# bms-interface_interface.net
KiCad netlist of a schematic drawn in Altium Designer
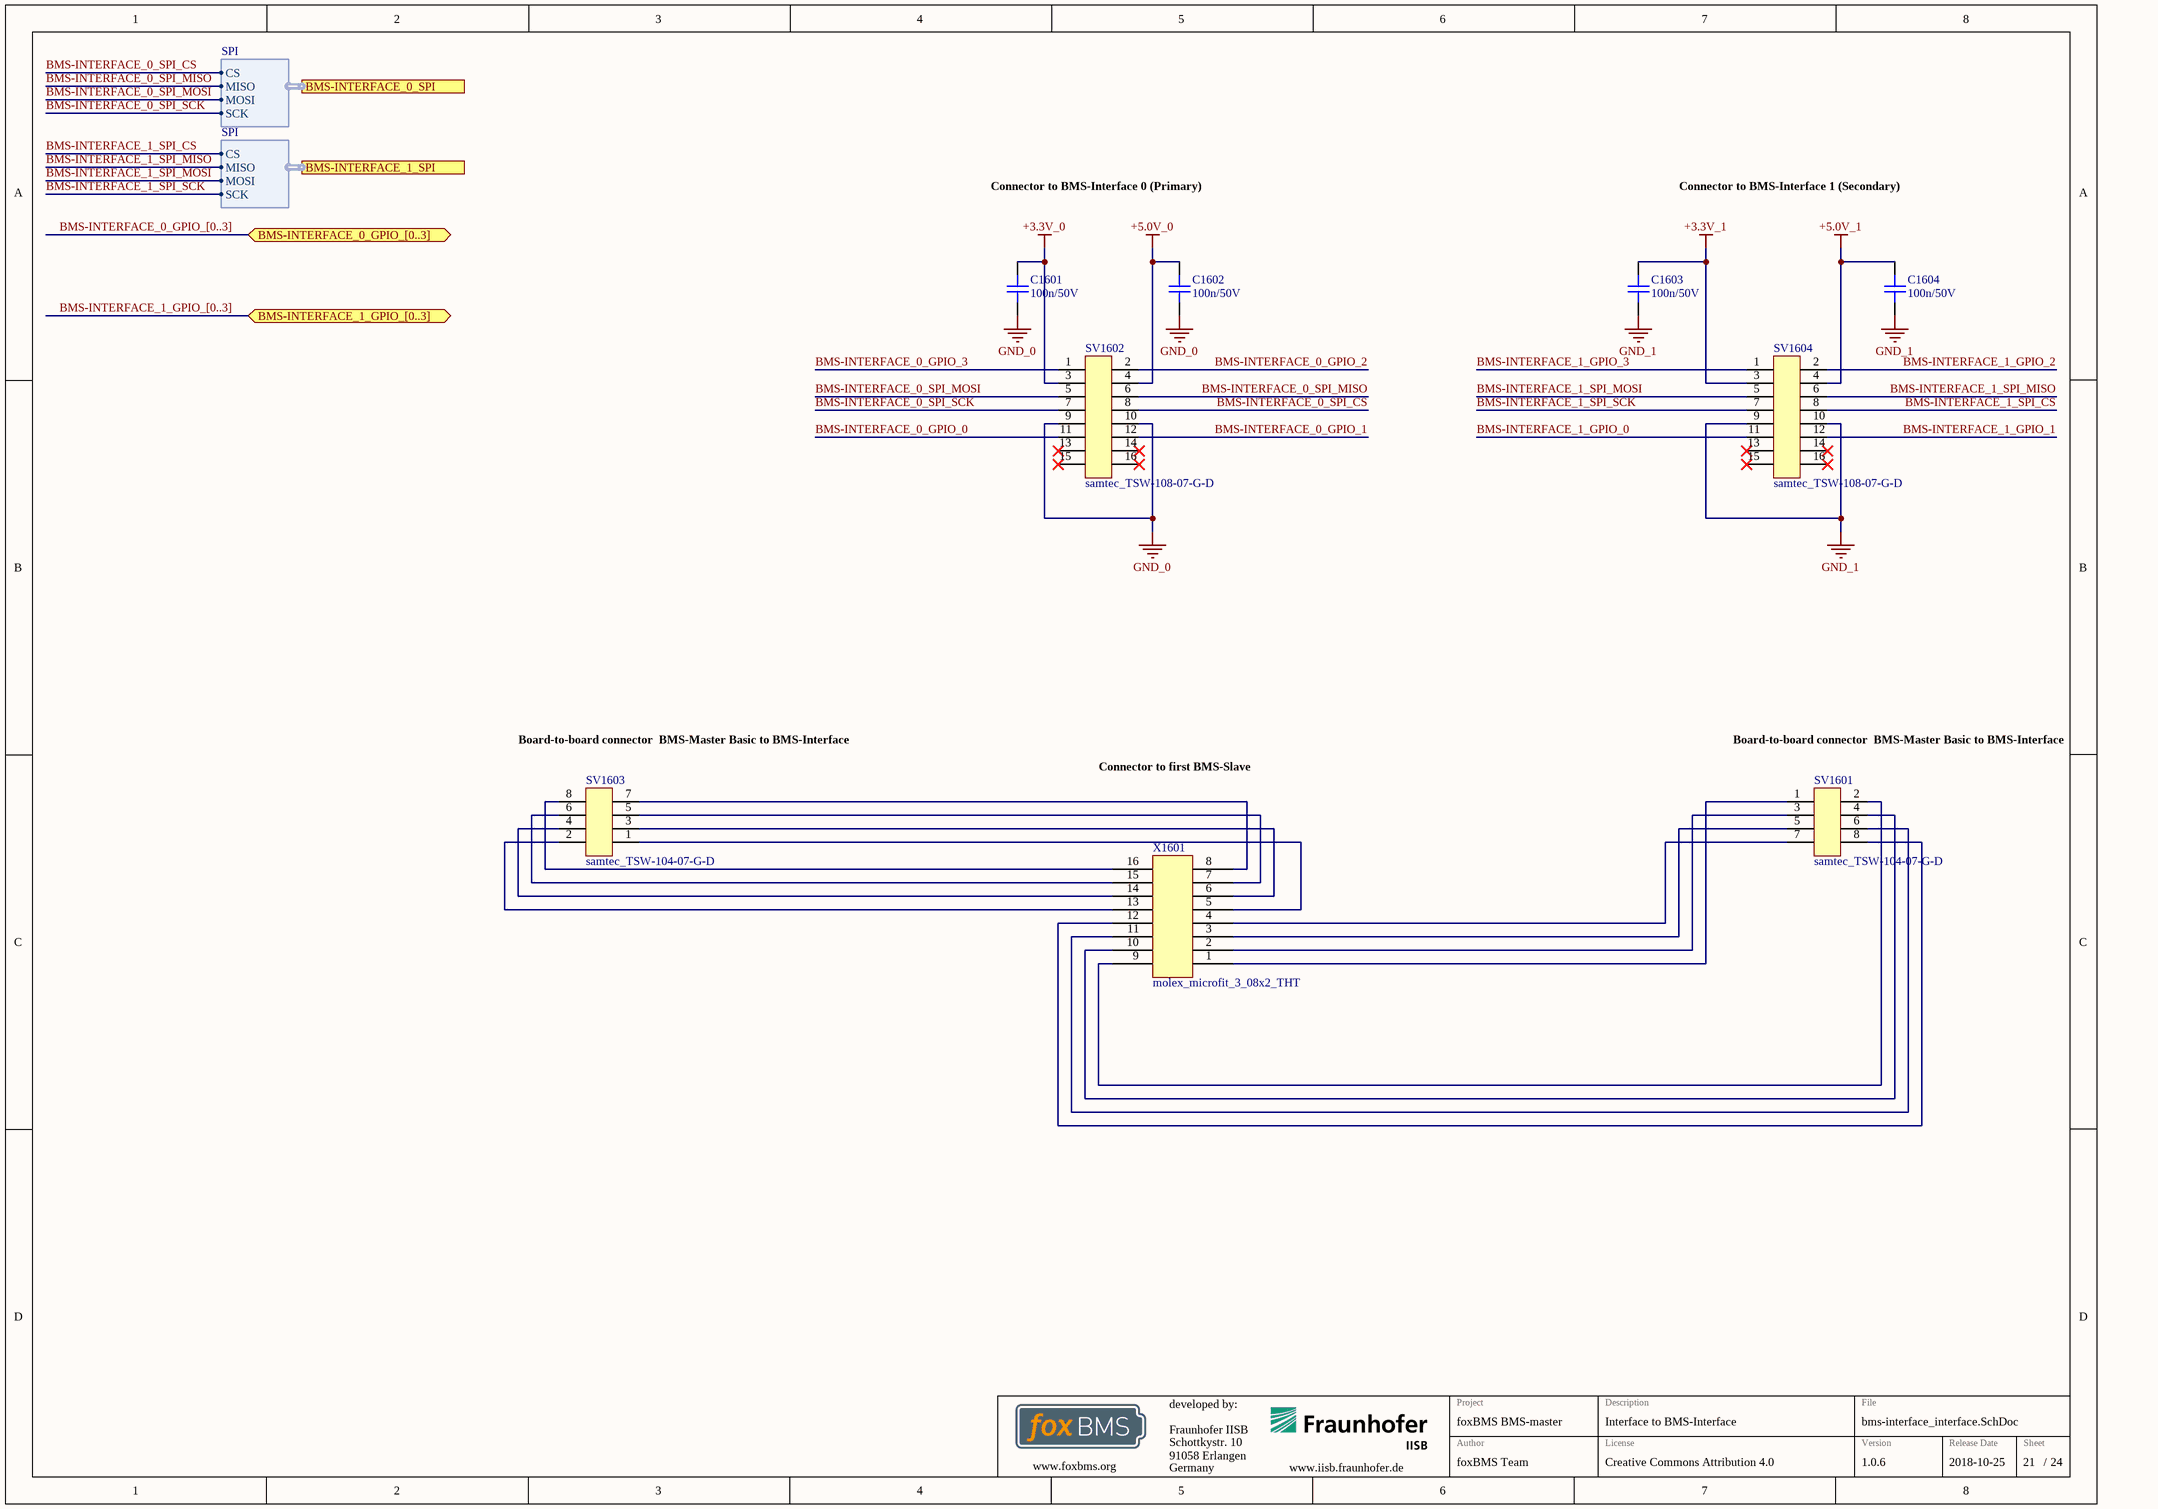
[diagram p0: bms-interface_interface.SchDoc]

(export (version "E")
  (design (tool "Eeschema 10.0.6"))
  (components
    (comp (ref "C1601")
      (value "100n/50V")
      (footprint "CAPC1608X08N")
      (description "MLCC")
      (fields (field (name "PART NUMBER") "gen_C_ceramic_100n_50V_X7R_0603"))
      (libsource (lib "OE750") (part "C"))
    )
    (comp (ref "C1602")
      (value "100n/50V")
      (footprint "CAPC1608X08N")
      (description "MLCC")
      (fields (field (name "PART NUMBER") "gen_C_ceramic_100n_50V_X7R_0603"))
      (libsource (lib "OE750") (part "C"))
    )
    (comp (ref "C1603")
      (value "100n/50V")
      (footprint "CAPC1608X08N")
      (description "MLCC")
      (fields (field (name "PART NUMBER") "gen_C_ceramic_100n_50V_X7R_0603"))
      (libsource (lib "OE750") (part "C"))
    )
    (comp (ref "C1604")
      (value "100n/50V")
      (footprint "CAPC1608X08N")
      (description "MLCC")
      (fields (field (name "PART NUMBER") "gen_C_ceramic_100n_50V_X7R_0603"))
      (libsource (lib "OE750") (part "C"))
    )
    (comp (ref "SV1601")
      (value "samtec_TSW-104-07-G-D")
      (footprint "Pinheader_2.54_2x4")
      (description "Board-To-Board Connector, Vertical, 2.54 mm, 8 Contacts, Header, TSW Series, Through Hole, 2 Rows")
      (fields (field (name "MANUFACTURER") "Samtec"))
      (libsource (lib "OE750") (part "X2x4"))
    )
    (comp (ref "SV1602")
      (value "samtec_TSW-108-07-G-D")
      (footprint "Pinheader_2.54_2x8")
      (description "Board-To-Board Connector, Vertical, 2.54 mm, 16 Contacts, Header, TSW Series, Through Hole, 2 Rows")
      (fields (field (name "MANUFACTURER") "Samtec"))
      (libsource (lib "OE750") (part "X2x8"))
    )
    (comp (ref "SV1603")
      (value "samtec_TSW-104-07-G-D")
      (footprint "Pinheader_2.54_2x4")
      (description "Board-To-Board Connector, Vertical, 2.54 mm, 8 Contacts, Header, TSW Series, Through Hole, 2 Rows")
      (fields (field (name "MANUFACTURER") "Samtec"))
      (libsource (lib "") (part "X2x4_1"))
    )
    (comp (ref "SV1604")
      (value "samtec_TSW-108-07-G-D")
      (footprint "Pinheader_2.54_2x8")
      (description "Board-To-Board Connector, Vertical, 2.54 mm, 16 Contacts, Header, TSW Series, Through Hole, 2 Rows")
      (fields (field (name "MANUFACTURER") "Samtec"))
      (libsource (lib "OE750") (part "X2x8"))
    )
    (comp (ref "X1601")
      (value "molex_microfit_3_08x2_THT")
      (footprint "MOLEX_MICROFIT_08x2_THT")
      (fields (field (name "MANUFACTURER") "Molex"))
      (libsource (lib "OE750") (part "X8x2"))
    )
  )
  (nets
    (net (code "2") (name "+3.3V_0") (class "Default")
      (node (ref "C1601") (pin "1") (pinfunction "1_1") (pintype "passive"))
      (node (ref "SV1602") (pin "3") (pintype "passive"))
    )
    (net (code "3") (name "+3.3V_1") (class "Default")
      (node (ref "C1603") (pin "1") (pinfunction "1_1") (pintype "passive"))
      (node (ref "SV1604") (pin "3") (pintype "passive"))
    )
    (net (code "4") (name "+5.0V_0") (class "Default")
      (node (ref "C1602") (pin "1") (pinfunction "1_1") (pintype "passive"))
      (node (ref "SV1602") (pin "4") (pintype "passive"))
    )
    (net (code "5") (name "+5.0V_1") (class "Default")
      (node (ref "C1604") (pin "1") (pinfunction "1_1") (pintype "passive"))
      (node (ref "SV1604") (pin "4") (pintype "passive"))
    )
    (net (code "6") (name "/BMS-INTERFACE_0_GPIO_0") (class "Default")
      (node (ref "SV1602") (pin "11") (pintype "passive"))
    )
    (net (code "7") (name "/BMS-INTERFACE_0_GPIO_1") (class "Default")
      (node (ref "SV1602") (pin "12") (pintype "passive"))
    )
    (net (code "8") (name "/BMS-INTERFACE_0_GPIO_2") (class "Default")
      (node (ref "SV1602") (pin "2") (pintype "passive"))
    )
    (net (code "9") (name "/BMS-INTERFACE_0_GPIO_3") (class "Default")
      (node (ref "SV1602") (pin "1") (pintype "passive"))
    )
    (net (code "11") (name "/BMS-INTERFACE_0_SPI_CS") (class "Default")
      (node (ref "SV1602") (pin "8") (pintype "passive"))
    )
    (net (code "12") (name "/BMS-INTERFACE_0_SPI_MISO") (class "Default")
      (node (ref "SV1602") (pin "6") (pintype "passive"))
    )
    (net (code "13") (name "/BMS-INTERFACE_0_SPI_MOSI") (class "Default")
      (node (ref "SV1602") (pin "5") (pintype "passive"))
    )
    (net (code "14") (name "/BMS-INTERFACE_0_SPI_SCK") (class "Default")
      (node (ref "SV1602") (pin "7") (pintype "passive"))
    )
    (net (code "15") (name "/BMS-INTERFACE_1_GPIO_0") (class "Default")
      (node (ref "SV1604") (pin "11") (pintype "passive"))
    )
    (net (code "16") (name "/BMS-INTERFACE_1_GPIO_1") (class "Default")
      (node (ref "SV1604") (pin "12") (pintype "passive"))
    )
    (net (code "17") (name "/BMS-INTERFACE_1_GPIO_2") (class "Default")
      (node (ref "SV1604") (pin "2") (pintype "passive"))
    )
    (net (code "18") (name "/BMS-INTERFACE_1_GPIO_3") (class "Default")
      (node (ref "SV1604") (pin "1") (pintype "passive"))
    )
    (net (code "20") (name "/BMS-INTERFACE_1_SPI_CS") (class "Default")
      (node (ref "SV1604") (pin "8") (pintype "passive"))
    )
    (net (code "21") (name "/BMS-INTERFACE_1_SPI_MISO") (class "Default")
      (node (ref "SV1604") (pin "6") (pintype "passive"))
    )
    (net (code "22") (name "/BMS-INTERFACE_1_SPI_MOSI") (class "Default")
      (node (ref "SV1604") (pin "5") (pintype "passive"))
    )
    (net (code "23") (name "/BMS-INTERFACE_1_SPI_SCK") (class "Default")
      (node (ref "SV1604") (pin "7") (pintype "passive"))
    )
    (net (code "25") (name "GND_0") (class "Default")
      (node (ref "C1601") (pin "2") (pinfunction "2_2") (pintype "passive"))
      (node (ref "C1602") (pin "2") (pinfunction "2_2") (pintype "passive"))
      (node (ref "SV1602") (pin "10") (pintype "passive"))
      (node (ref "SV1602") (pin "9") (pintype "passive"))
    )
    (net (code "26") (name "GND_1") (class "Default")
      (node (ref "C1603") (pin "2") (pinfunction "2_2") (pintype "passive"))
      (node (ref "C1604") (pin "2") (pinfunction "2_2") (pintype "passive"))
      (node (ref "SV1604") (pin "10") (pintype "passive"))
      (node (ref "SV1604") (pin "9") (pintype "passive"))
    )
    (net (code "27") (name "Net-(SV1601-Pad1)") (class "Default")
      (node (ref "SV1601") (pin "1") (pintype "passive"))
      (node (ref "X1601") (pin "1") (pintype "passive"))
    )
    (net (code "28") (name "Net-(SV1601-Pad2)") (class "Default")
      (node (ref "SV1601") (pin "2") (pintype "passive"))
      (node (ref "X1601") (pin "9") (pintype "passive"))
    )
    (net (code "29") (name "Net-(SV1601-Pad3)") (class "Default")
      (node (ref "SV1601") (pin "3") (pintype "passive"))
      (node (ref "X1601") (pin "2") (pintype "passive"))
    )
    (net (code "30") (name "Net-(SV1601-Pad4)") (class "Default")
      (node (ref "SV1601") (pin "4") (pintype "passive"))
      (node (ref "X1601") (pin "10") (pintype "passive"))
    )
    (net (code "31") (name "Net-(SV1601-Pad5)") (class "Default")
      (node (ref "SV1601") (pin "5") (pintype "passive"))
      (node (ref "X1601") (pin "3") (pintype "passive"))
    )
    (net (code "32") (name "Net-(SV1601-Pad6)") (class "Default")
      (node (ref "SV1601") (pin "6") (pintype "passive"))
      (node (ref "X1601") (pin "11") (pintype "passive"))
    )
    (net (code "33") (name "Net-(SV1601-Pad7)") (class "Default")
      (node (ref "SV1601") (pin "7") (pintype "passive"))
      (node (ref "X1601") (pin "4") (pintype "passive"))
    )
    (net (code "34") (name "Net-(SV1601-Pad8)") (class "Default")
      (node (ref "SV1601") (pin "8") (pintype "passive"))
      (node (ref "X1601") (pin "12") (pintype "passive"))
    )
    (net (code "35") (name "Net-(SV1603-Pad1)") (class "Default")
      (node (ref "SV1603") (pin "1") (pintype "passive"))
      (node (ref "X1601") (pin "5") (pintype "passive"))
    )
    (net (code "36") (name "Net-(SV1603-Pad2)") (class "Default")
      (node (ref "SV1603") (pin "2") (pintype "passive"))
      (node (ref "X1601") (pin "13") (pintype "passive"))
    )
    (net (code "37") (name "Net-(SV1603-Pad3)") (class "Default")
      (node (ref "SV1603") (pin "3") (pintype "passive"))
      (node (ref "X1601") (pin "6") (pintype "passive"))
    )
    (net (code "38") (name "Net-(SV1603-Pad4)") (class "Default")
      (node (ref "SV1603") (pin "4") (pintype "passive"))
      (node (ref "X1601") (pin "14") (pintype "passive"))
    )
    (net (code "39") (name "Net-(SV1603-Pad5)") (class "Default")
      (node (ref "SV1603") (pin "5") (pintype "passive"))
      (node (ref "X1601") (pin "7") (pintype "passive"))
    )
    (net (code "40") (name "Net-(SV1603-Pad6)") (class "Default")
      (node (ref "SV1603") (pin "6") (pintype "passive"))
      (node (ref "X1601") (pin "15") (pintype "passive"))
    )
    (net (code "41") (name "Net-(SV1603-Pad7)") (class "Default")
      (node (ref "SV1603") (pin "7") (pintype "passive"))
      (node (ref "X1601") (pin "8") (pintype "passive"))
    )
    (net (code "42") (name "Net-(SV1603-Pad8)") (class "Default")
      (node (ref "SV1603") (pin "8") (pintype "passive"))
      (node (ref "X1601") (pin "16") (pintype "passive"))
    )
    (net (code "43") (name "unconnected-(SV1602-Pad13)") (class "Default")
      (node (ref "SV1602") (pin "13") (pintype "passive+no_connect"))
    )
    (net (code "44") (name "unconnected-(SV1602-Pad14)") (class "Default")
      (node (ref "SV1602") (pin "14") (pintype "passive+no_connect"))
    )
    (net (code "45") (name "unconnected-(SV1602-Pad15)") (class "Default")
      (node (ref "SV1602") (pin "15") (pintype "passive+no_connect"))
    )
    (net (code "46") (name "unconnected-(SV1602-Pad16)") (class "Default")
      (node (ref "SV1602") (pin "16") (pintype "passive+no_connect"))
    )
    (net (code "47") (name "unconnected-(SV1604-Pad13)") (class "Default")
      (node (ref "SV1604") (pin "13") (pintype "passive+no_connect"))
    )
    (net (code "48") (name "unconnected-(SV1604-Pad14)") (class "Default")
      (node (ref "SV1604") (pin "14") (pintype "passive+no_connect"))
    )
    (net (code "49") (name "unconnected-(SV1604-Pad15)") (class "Default")
      (node (ref "SV1604") (pin "15") (pintype "passive+no_connect"))
    )
    (net (code "50") (name "unconnected-(SV1604-Pad16)") (class "Default")
      (node (ref "SV1604") (pin "16") (pintype "passive+no_connect"))
    )
  )
)
